# cs301_YourGroupNumber---------------.net
KiCad netlist of a schematic drawn in Altium Designer
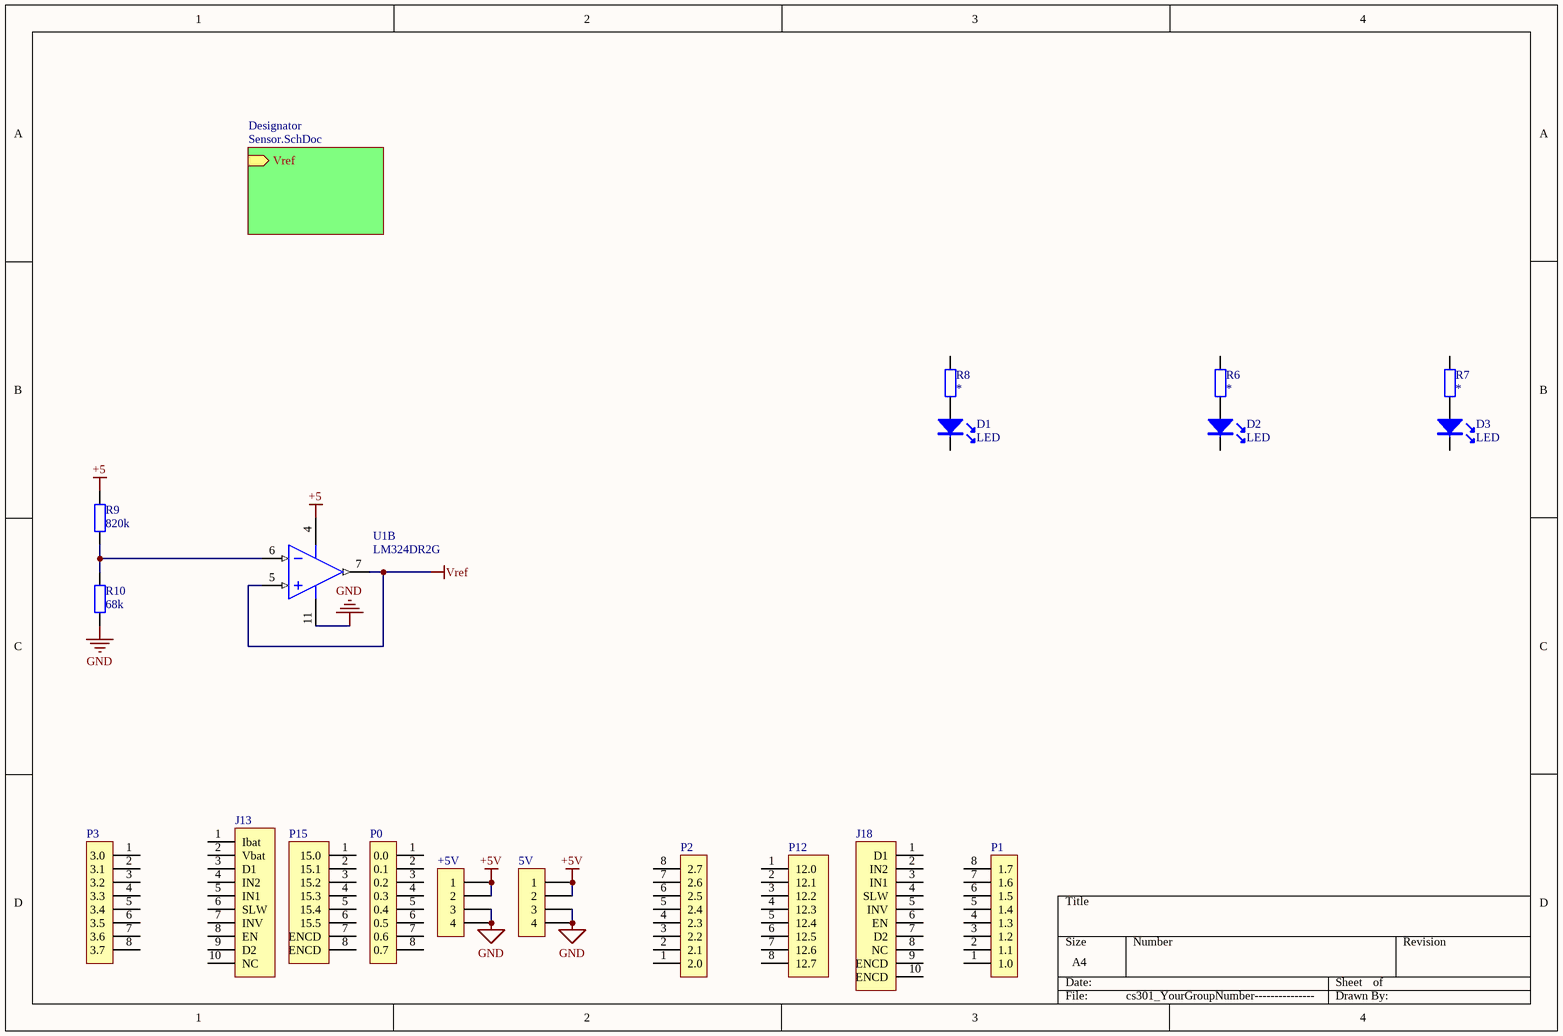
[diagram p0: cs301_YourGroupNumber---------------.SchDoc]

(export (version "E")
  (design (tool "Eeschema 10.0.6"))
  (components
    (comp (ref "+5V")
      (value "5V")
      (footprint "IDC4")
      (description "Connector")
      (libsource (lib "Miscellaneous Devices") (part "CON4"))
    )
    (comp (ref "5V")
      (value "5V")
      (footprint "IDC4")
      (description "Connector")
      (libsource (lib "Miscellaneous Devices") (part "CON4"))
    )
    (comp (ref "D1") (value "LED") (footprint "LED0.1/5MM") (libsource (lib "COMSYS301_2013") (part "LED")))
    (comp (ref "D2") (value "LED") (footprint "LED0.1/5MM") (libsource (lib "COMSYS301_2013") (part "LED")))
    (comp (ref "D3") (value "LED") (footprint "LED0.1/5MM") (libsource (lib "COMSYS301_2013") (part "LED")))
    (comp (ref "J13")
      (value "CON10")
      (footprint "idc10")
      (description "Connector")
      (libsource (lib "") (part "CON10_1"))
    )
    (comp (ref "J18")
      (value "CON10")
      (footprint "IDC10")
      (description "Connector")
      (libsource (lib "Miscellaneous Devices") (part "CON10"))
    )
    (comp (ref "P0")
      (value "P0")
      (footprint "idc8")
      (description "Connector")
      (libsource (lib "") (part "CON8_1"))
    )
    (comp (ref "P1")
      (value "P1")
      (footprint "idc8")
      (description "Connector")
      (libsource (lib "Miscellaneous Devices") (part "CON8"))
    )
    (comp (ref "P2")
      (value "P2")
      (footprint "idc8")
      (description "Connector")
      (libsource (lib "") (part "CON8_2"))
    )
    (comp (ref "P3")
      (value "P3")
      (footprint "idc8")
      (description "Connector")
      (libsource (lib "") (part "CON8_1"))
    )
    (comp (ref "P12")
      (value "P12")
      (footprint "idc8")
      (description "Connector")
      (libsource (lib "Miscellaneous Devices") (part "CON8_1"))
    )
    (comp (ref "P15")
      (value "P15")
      (footprint "idc8")
      (description "Connector")
      (libsource (lib "") (part "CON8_1_1"))
    )
    (comp (ref "R6")
      (value "*")
      (footprint "0805 RES")
      (description "0805 resistor")
      (fields (field (name "PUBLISHER") "Altium Limited"))
      (libsource (lib "EE209_Library") (part "Res_SMT_0805"))
    )
    (comp (ref "R7")
      (value "*")
      (footprint "0805 RES")
      (description "0805 resistor")
      (fields (field (name "PUBLISHER") "Altium Limited"))
      (libsource (lib "EE209_Library") (part "Res_SMT_0805"))
    )
    (comp (ref "R8")
      (value "*")
      (footprint "0805 RES")
      (description "0805 resistor")
      (fields (field (name "PUBLISHER") "Altium Limited"))
      (libsource (lib "EE209_Library") (part "Res_SMT_0805"))
    )
    (comp (ref "R9")
      (value "820k")
      (footprint "0805 RES")
      (description "0805 resistor")
      (fields (field (name "PUBLISHER") "Altium Limited"))
      (libsource (lib "EE209_Library") (part "Res_SMT_0805"))
    )
    (comp (ref "R10")
      (value "68k")
      (footprint "0805 RES")
      (description "0805 resistor")
      (fields (field (name "PUBLISHER") "Altium Limited"))
      (libsource (lib "EE209_Library") (part "Res_SMT_0805"))
    )
    (comp (ref "U1")
      (value "LM324DR2G")
      (footprint "SOIC-14")
      (fields (field (name "MANUFACTURER") "On Semiconductor"))
      (libsource (lib "EE209_Library") (part "LM324DR_SMT_SOIC16"))
    )
  )
  (nets
    (net (code "1") (name "+5") (class "Default")
      (node (ref "R9") (pin "2") (pinfunction "2_2") (pintype "passive"))
      (node (ref "U1") (pin "4") (pinfunction "VCC_4") (pintype "power_in"))
    )
    (net (code "2") (name "+5V") (class "Default")
      (node (ref "+5V") (pin "1") (pinfunction "1_1") (pintype "passive"))
      (node (ref "+5V") (pin "2") (pinfunction "2_2") (pintype "passive"))
      (node (ref "5V") (pin "1") (pinfunction "1_1") (pintype "passive"))
      (node (ref "5V") (pin "2") (pinfunction "2_2") (pintype "passive"))
    )
    (net (code "4") (name "GND") (class "Default")
      (node (ref "+5V") (pin "3") (pinfunction "3_3") (pintype "passive"))
      (node (ref "+5V") (pin "4") (pinfunction "4_4") (pintype "passive"))
      (node (ref "5V") (pin "3") (pinfunction "3_3") (pintype "passive"))
      (node (ref "5V") (pin "4") (pinfunction "4_4") (pintype "passive"))
      (node (ref "R10") (pin "1") (pinfunction "1_1") (pintype "passive"))
      (node (ref "U1") (pin "11") (pinfunction "VEE/GND_11") (pintype "power_in"))
    )
    (net (code "5") (name "Net-(D1-1)") (class "Default")
      (node (ref "D1") (pin "A") (pinfunction "1_A") (pintype "passive"))
      (node (ref "R8") (pin "1") (pinfunction "1_1") (pintype "passive"))
    )
    (net (code "6") (name "Net-(D2-1)") (class "Default")
      (node (ref "D2") (pin "A") (pinfunction "1_A") (pintype "passive"))
      (node (ref "R6") (pin "1") (pinfunction "1_1") (pintype "passive"))
    )
    (net (code "7") (name "Net-(D3-1)") (class "Default")
      (node (ref "D3") (pin "A") (pinfunction "1_A") (pintype "passive"))
      (node (ref "R7") (pin "1") (pinfunction "1_1") (pintype "passive"))
    )
    (net (code "8") (name "Net-(U1B-IN2-)") (class "Default")
      (node (ref "R10") (pin "2") (pinfunction "2_2") (pintype "passive"))
      (node (ref "R9") (pin "1") (pinfunction "1_1") (pintype "passive"))
      (node (ref "U1") (pin "6") (pinfunction "IN2-_6") (pintype "input"))
    )
    (net (code "9") (name "Vref") (class "Default")
      (node (ref "U1") (pin "5") (pinfunction "IN2+_5") (pintype "input"))
      (node (ref "U1") (pin "7") (pinfunction "OUT2_7") (pintype "output"))
    )
    (net (code "10") (name "unconnected-(D1-2-PadK)") (class "Default")
      (node (ref "D1") (pin "K") (pinfunction "2_K") (pintype "passive"))
    )
    (net (code "11") (name "unconnected-(D2-2-PadK)") (class "Default")
      (node (ref "D2") (pin "K") (pinfunction "2_K") (pintype "passive"))
    )
    (net (code "12") (name "unconnected-(D3-2-PadK)") (class "Default")
      (node (ref "D3") (pin "K") (pinfunction "2_K") (pintype "passive"))
    )
    (net (code "13") (name "unconnected-(J13-D1-Pad3)") (class "Default")
      (node (ref "J13") (pin "3") (pinfunction "D1_3") (pintype "passive"))
    )
    (net (code "14") (name "unconnected-(J13-D2-Pad9)") (class "Default")
      (node (ref "J13") (pin "9") (pinfunction "D2_9") (pintype "passive"))
    )
    (net (code "15") (name "unconnected-(J13-EN-Pad8)") (class "Default")
      (node (ref "J13") (pin "8") (pinfunction "EN_8") (pintype "passive"))
    )
    (net (code "16") (name "unconnected-(J13-IN1-Pad5)") (class "Default")
      (node (ref "J13") (pin "5") (pinfunction "IN1_5") (pintype "passive"))
    )
    (net (code "17") (name "unconnected-(J13-IN2-Pad4)") (class "Default")
      (node (ref "J13") (pin "4") (pinfunction "IN2_4") (pintype "passive"))
    )
    (net (code "18") (name "unconnected-(J13-INV-Pad7)") (class "Default")
      (node (ref "J13") (pin "7") (pinfunction "INV_7") (pintype "passive"))
    )
    (net (code "19") (name "unconnected-(J13-Ibat-Pad1)") (class "Default")
      (node (ref "J13") (pin "1") (pinfunction "Ibat_1") (pintype "passive"))
    )
    (net (code "20") (name "unconnected-(J13-NC-Pad10)") (class "Default")
      (node (ref "J13") (pin "10") (pinfunction "NC_10") (pintype "passive"))
    )
    (net (code "21") (name "unconnected-(J13-SLW-Pad6)") (class "Default")
      (node (ref "J13") (pin "6") (pinfunction "SLW_6") (pintype "passive"))
    )
    (net (code "22") (name "unconnected-(J13-Vbat-Pad2)") (class "Default")
      (node (ref "J13") (pin "2") (pinfunction "Vbat_2") (pintype "passive"))
    )
    (net (code "23") (name "unconnected-(J18-D1-Pad1)") (class "Default")
      (node (ref "J18") (pin "1") (pinfunction "D1_1") (pintype "passive"))
    )
    (net (code "24") (name "unconnected-(J18-D2-Pad7)") (class "Default")
      (node (ref "J18") (pin "7") (pinfunction "D2_7") (pintype "passive"))
    )
    (net (code "25") (name "unconnected-(J18-EN-Pad6)") (class "Default")
      (node (ref "J18") (pin "6") (pinfunction "EN_6") (pintype "passive"))
    )
    (net (code "26") (name "unconnected-(J18-ENCD-Pad9)") (class "Default")
      (node (ref "J18") (pin "9") (pinfunction "ENCD_9") (pintype "passive"))
    )
    (net (code "27") (name "unconnected-(J18-ENCD-Pad10)") (class "Default")
      (node (ref "J18") (pin "10") (pinfunction "ENCD_10") (pintype "passive"))
    )
    (net (code "28") (name "unconnected-(J18-IN1-Pad3)") (class "Default")
      (node (ref "J18") (pin "3") (pinfunction "IN1_3") (pintype "passive"))
    )
    (net (code "29") (name "unconnected-(J18-IN2-Pad2)") (class "Default")
      (node (ref "J18") (pin "2") (pinfunction "IN2_2") (pintype "passive"))
    )
    (net (code "30") (name "unconnected-(J18-INV-Pad5)") (class "Default")
      (node (ref "J18") (pin "5") (pinfunction "INV_5") (pintype "passive"))
    )
    (net (code "31") (name "unconnected-(J18-NC-Pad8)") (class "Default")
      (node (ref "J18") (pin "8") (pinfunction "NC_8") (pintype "passive"))
    )
    (net (code "32") (name "unconnected-(J18-SLW-Pad4)") (class "Default")
      (node (ref "J18") (pin "4") (pinfunction "SLW_4") (pintype "passive"))
    )
    (net (code "33") (name "unconnected-(P0-3.0-Pad1)") (class "Default")
      (node (ref "P0") (pin "1") (pinfunction "3.0_1") (pintype "passive"))
    )
    (net (code "34") (name "unconnected-(P0-3.1-Pad2)") (class "Default")
      (node (ref "P0") (pin "2") (pinfunction "3.1_2") (pintype "passive"))
    )
    (net (code "35") (name "unconnected-(P0-3.2-Pad3)") (class "Default")
      (node (ref "P0") (pin "3") (pinfunction "3.2_3") (pintype "passive"))
    )
    (net (code "36") (name "unconnected-(P0-3.3-Pad4)") (class "Default")
      (node (ref "P0") (pin "4") (pinfunction "3.3_4") (pintype "passive"))
    )
    (net (code "37") (name "unconnected-(P0-3.4-Pad5)") (class "Default")
      (node (ref "P0") (pin "5") (pinfunction "3.4_5") (pintype "passive"))
    )
    (net (code "38") (name "unconnected-(P0-3.5-Pad6)") (class "Default")
      (node (ref "P0") (pin "6") (pinfunction "3.5_6") (pintype "passive"))
    )
    (net (code "39") (name "unconnected-(P0-3.6-Pad7)") (class "Default")
      (node (ref "P0") (pin "7") (pinfunction "3.6_7") (pintype "passive"))
    )
    (net (code "40") (name "unconnected-(P0-3.7-Pad8)") (class "Default")
      (node (ref "P0") (pin "8") (pinfunction "3.7_8") (pintype "passive"))
    )
    (net (code "41") (name "unconnected-(P1-1.0-Pad1)") (class "Default")
      (node (ref "P1") (pin "1") (pinfunction "1.0_1") (pintype "passive"))
    )
    (net (code "42") (name "unconnected-(P1-1.1-Pad2)") (class "Default")
      (node (ref "P1") (pin "2") (pinfunction "1.1_2") (pintype "passive"))
    )
    (net (code "43") (name "unconnected-(P1-1.2-Pad3)") (class "Default")
      (node (ref "P1") (pin "3") (pinfunction "1.2_3") (pintype "passive"))
    )
    (net (code "44") (name "unconnected-(P1-1.3-Pad4)") (class "Default")
      (node (ref "P1") (pin "4") (pinfunction "1.3_4") (pintype "passive"))
    )
    (net (code "45") (name "unconnected-(P1-1.4-Pad5)") (class "Default")
      (node (ref "P1") (pin "5") (pinfunction "1.4_5") (pintype "passive"))
    )
    (net (code "46") (name "unconnected-(P1-1.5-Pad6)") (class "Default")
      (node (ref "P1") (pin "6") (pinfunction "1.5_6") (pintype "passive"))
    )
    (net (code "47") (name "unconnected-(P1-1.6-Pad7)") (class "Default")
      (node (ref "P1") (pin "7") (pinfunction "1.6_7") (pintype "passive"))
    )
    (net (code "48") (name "unconnected-(P1-1.7-Pad8)") (class "Default")
      (node (ref "P1") (pin "8") (pinfunction "1.7_8") (pintype "passive"))
    )
    (net (code "49") (name "unconnected-(P2-2.0-Pad1)") (class "Default")
      (node (ref "P2") (pin "1") (pinfunction "2.0_1") (pintype "passive"))
    )
    (net (code "50") (name "unconnected-(P2-2.1-Pad2)") (class "Default")
      (node (ref "P2") (pin "2") (pinfunction "2.1_2") (pintype "passive"))
    )
    (net (code "51") (name "unconnected-(P2-2.2-Pad3)") (class "Default")
      (node (ref "P2") (pin "3") (pinfunction "2.2_3") (pintype "passive"))
    )
    (net (code "52") (name "unconnected-(P2-2.3-Pad4)") (class "Default")
      (node (ref "P2") (pin "4") (pinfunction "2.3_4") (pintype "passive"))
    )
    (net (code "53") (name "unconnected-(P2-2.4-Pad5)") (class "Default")
      (node (ref "P2") (pin "5") (pinfunction "2.4_5") (pintype "passive"))
    )
    (net (code "54") (name "unconnected-(P2-2.5-Pad6)") (class "Default")
      (node (ref "P2") (pin "6") (pinfunction "2.5_6") (pintype "passive"))
    )
    (net (code "55") (name "unconnected-(P2-2.6-Pad7)") (class "Default")
      (node (ref "P2") (pin "7") (pinfunction "2.6_7") (pintype "passive"))
    )
    (net (code "56") (name "unconnected-(P2-2.7-Pad8)") (class "Default")
      (node (ref "P2") (pin "8") (pinfunction "2.7_8") (pintype "passive"))
    )
    (net (code "57") (name "unconnected-(P3-3.0-Pad1)") (class "Default")
      (node (ref "P3") (pin "1") (pinfunction "3.0_1") (pintype "passive"))
    )
    (net (code "58") (name "unconnected-(P3-3.1-Pad2)") (class "Default")
      (node (ref "P3") (pin "2") (pinfunction "3.1_2") (pintype "passive"))
    )
    (net (code "59") (name "unconnected-(P3-3.2-Pad3)") (class "Default")
      (node (ref "P3") (pin "3") (pinfunction "3.2_3") (pintype "passive"))
    )
    (net (code "60") (name "unconnected-(P3-3.3-Pad4)") (class "Default")
      (node (ref "P3") (pin "4") (pinfunction "3.3_4") (pintype "passive"))
    )
    (net (code "61") (name "unconnected-(P3-3.4-Pad5)") (class "Default")
      (node (ref "P3") (pin "5") (pinfunction "3.4_5") (pintype "passive"))
    )
    (net (code "62") (name "unconnected-(P3-3.5-Pad6)") (class "Default")
      (node (ref "P3") (pin "6") (pinfunction "3.5_6") (pintype "passive"))
    )
    (net (code "63") (name "unconnected-(P3-3.6-Pad7)") (class "Default")
      (node (ref "P3") (pin "7") (pinfunction "3.6_7") (pintype "passive"))
    )
    (net (code "64") (name "unconnected-(P3-3.7-Pad8)") (class "Default")
      (node (ref "P3") (pin "8") (pinfunction "3.7_8") (pintype "passive"))
    )
    (net (code "65") (name "unconnected-(P12-12.0-Pad1)") (class "Default")
      (node (ref "P12") (pin "1") (pinfunction "12.0_1") (pintype "passive"))
    )
    (net (code "66") (name "unconnected-(P12-12.1-Pad2)") (class "Default")
      (node (ref "P12") (pin "2") (pinfunction "12.1_2") (pintype "passive"))
    )
    (net (code "67") (name "unconnected-(P12-12.2-Pad3)") (class "Default")
      (node (ref "P12") (pin "3") (pinfunction "12.2_3") (pintype "passive"))
    )
    (net (code "68") (name "unconnected-(P12-12.3-Pad4)") (class "Default")
      (node (ref "P12") (pin "4") (pinfunction "12.3_4") (pintype "passive"))
    )
    (net (code "69") (name "unconnected-(P12-12.4-Pad5)") (class "Default")
      (node (ref "P12") (pin "5") (pinfunction "12.4_5") (pintype "passive"))
    )
    (net (code "70") (name "unconnected-(P12-12.5-Pad6)") (class "Default")
      (node (ref "P12") (pin "6") (pinfunction "12.5_6") (pintype "passive"))
    )
    (net (code "71") (name "unconnected-(P12-12.6-Pad7)") (class "Default")
      (node (ref "P12") (pin "7") (pinfunction "12.6_7") (pintype "passive"))
    )
    (net (code "72") (name "unconnected-(P12-12.7-Pad8)") (class "Default")
      (node (ref "P12") (pin "8") (pinfunction "12.7_8") (pintype "passive"))
    )
    (net (code "73") (name "unconnected-(P15-15.0-Pad1)") (class "Default")
      (node (ref "P15") (pin "1") (pinfunction "15.0_1") (pintype "passive"))
    )
    (net (code "74") (name "unconnected-(P15-15.1-Pad2)") (class "Default")
      (node (ref "P15") (pin "2") (pinfunction "15.1_2") (pintype "passive"))
    )
    (net (code "75") (name "unconnected-(P15-15.2-Pad3)") (class "Default")
      (node (ref "P15") (pin "3") (pinfunction "15.2_3") (pintype "passive"))
    )
    (net (code "76") (name "unconnected-(P15-15.3-Pad4)") (class "Default")
      (node (ref "P15") (pin "4") (pinfunction "15.3_4") (pintype "passive"))
    )
    (net (code "77") (name "unconnected-(P15-15.4-Pad5)") (class "Default")
      (node (ref "P15") (pin "5") (pinfunction "15.4_5") (pintype "passive"))
    )
    (net (code "78") (name "unconnected-(P15-15.5-Pad6)") (class "Default")
      (node (ref "P15") (pin "6") (pinfunction "15.5_6") (pintype "passive"))
    )
    (net (code "79") (name "unconnected-(P15-ENCD-Pad7)") (class "Default")
      (node (ref "P15") (pin "7") (pinfunction "ENCD_7") (pintype "passive"))
    )
    (net (code "80") (name "unconnected-(P15-ENCD-Pad8)") (class "Default")
      (node (ref "P15") (pin "8") (pinfunction "ENCD_8") (pintype "passive"))
    )
    (net (code "81") (name "unconnected-(R6-Pad2)") (class "Default")
      (node (ref "R6") (pin "2") (pinfunction "2_2") (pintype "passive"))
    )
    (net (code "82") (name "unconnected-(R7-Pad2)") (class "Default")
      (node (ref "R7") (pin "2") (pinfunction "2_2") (pintype "passive"))
    )
    (net (code "83") (name "unconnected-(R8-Pad2)") (class "Default")
      (node (ref "R8") (pin "2") (pinfunction "2_2") (pintype "passive"))
    )
  )
)
